# Actuadores.net
KiCad netlist of a schematic drawn in Altium Designer
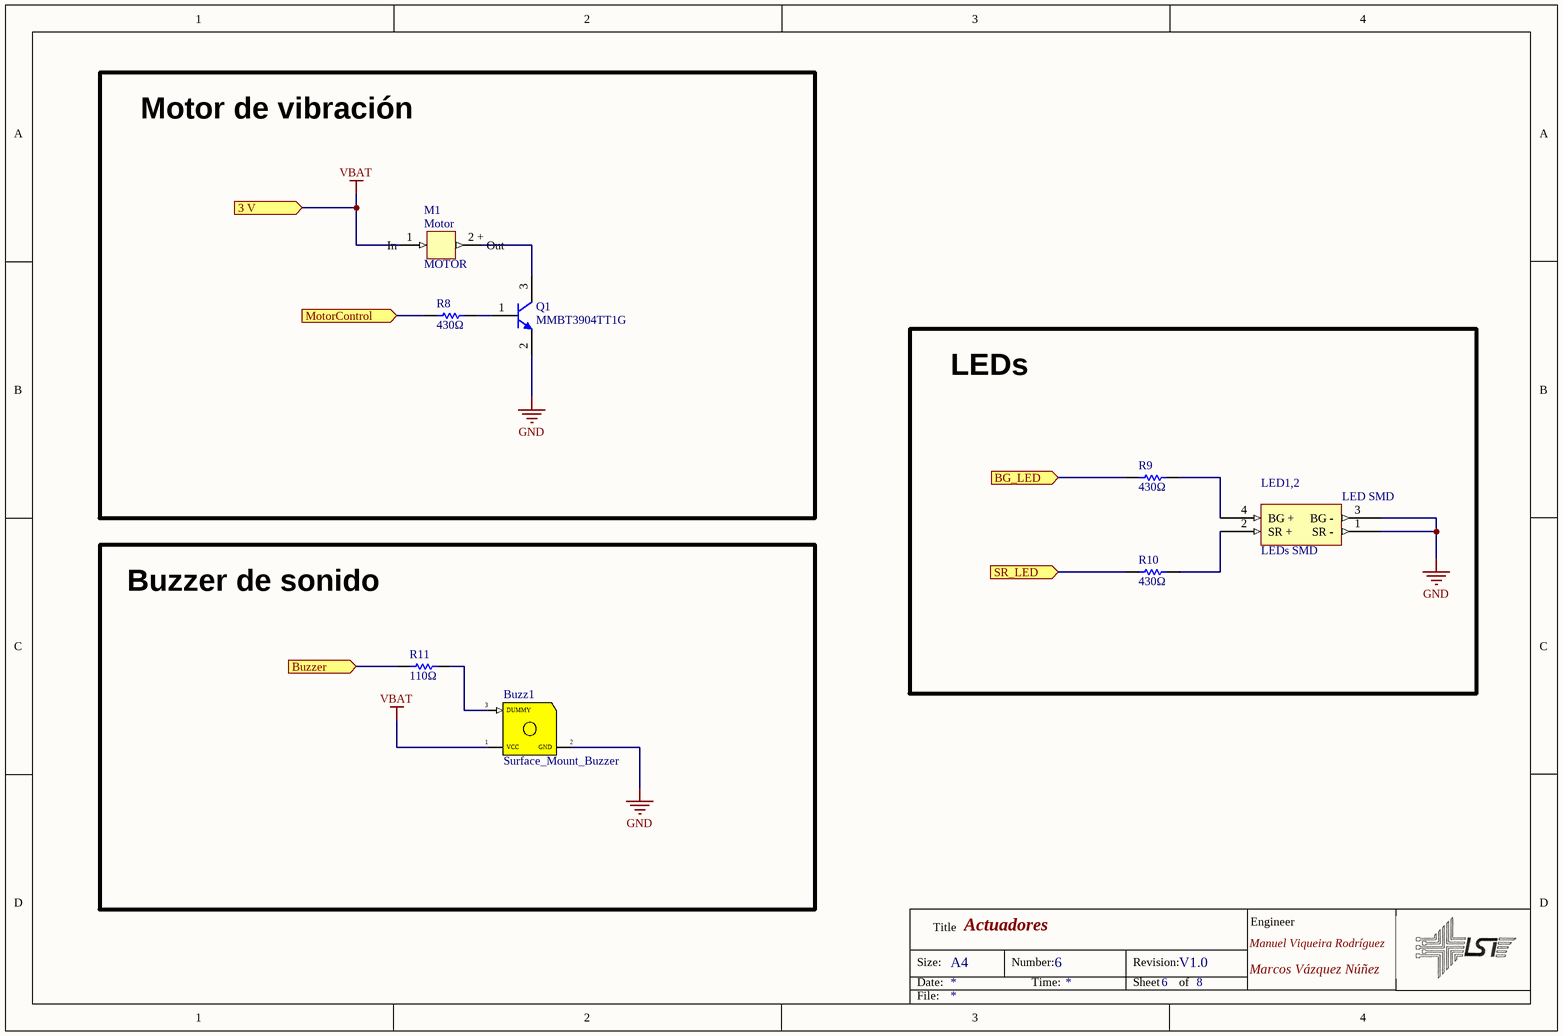
[diagram p0: Actuadores.SchDoc]

(export (version "E")
  (design (tool "Eeschema 10.0.6"))
  (components
    (comp (ref "Buzz1")
      (value "Surface_Mount_Buzzer")
      (footprint "buzzer")
      (libsource (lib "DEOP2021") (part "Surface_Mount_Buzzer"))
    )
    (comp (ref "LED1,2") (value "LEDs SMD") (footprint "LED_SMD") (libsource (lib "DEOP2021") (part "LED")))
    (comp (ref "M1") (value "MOTOR") (footprint "Motor") (libsource (lib "DEOP2021") (part "MOTOR")))
    (comp (ref "Q1")
      (value "MMBT3904TT1G")
      (footprint "ONSC-SC-75-3-463-01_V")
      (description "General Purpose Transistor, NPN Silicon, 3-Pin SC-75, Pb-Free, Tape and Reel")
      (fields (field (name "MANUFACTURER") "On Semiconductor"))
      (libsource (lib "Altium Content Vault") (part "ONSC-NPN-B1E2C3-3"))
    )
    (comp (ref "R8")
      (value "430Ω")
      (footprint "RESC0603X28X15ML05T05")
      (fields (field (name "MANUFACTURER") "Vishay Dale") (field (name "PART NUMBER") "CRCW020120K0JNED"))
      (libsource (lib "Altium Content Vault") (part "RES"))
    )
    (comp (ref "R9")
      (value "430Ω")
      (footprint "RESC0603X28X15ML05T05")
      (fields (field (name "MANUFACTURER") "Vishay Dale") (field (name "PART NUMBER") "CRCW020120K0JNED"))
      (libsource (lib "Altium Content Vault") (part "RES"))
    )
    (comp (ref "R10")
      (value "430Ω")
      (footprint "RESC0603X28X15ML05T05")
      (fields (field (name "MANUFACTURER") "Vishay Dale") (field (name "PART NUMBER") "CRCW020120K0JNED"))
      (libsource (lib "Altium Content Vault") (part "RES"))
    )
    (comp (ref "R11")
      (value "110Ω")
      (footprint "RESC0603X28X15ML05T05")
      (fields (field (name "MANUFACTURER") "Vishay Dale") (field (name "PART NUMBER") "CRCW020120K0JNED"))
      (libsource (lib "Altium Content Vault") (part "RES"))
    )
  )
  (nets
    (net (code "1") (name "/BG_LED") (class "Default")
      (node (ref "R9") (pin "1") (pinfunction "1_1") (pintype "passive"))
    )
    (net (code "2") (name "/Buzzer") (class "Default")
      (node (ref "R11") (pin "1") (pinfunction "1_1") (pintype "passive"))
    )
    (net (code "3") (name "/MotorControl") (class "Default")
      (node (ref "R8") (pin "1") (pinfunction "1_1") (pintype "passive"))
    )
    (net (code "4") (name "/SR_LED") (class "Default")
      (node (ref "R10") (pin "1") (pinfunction "1_1") (pintype "passive"))
    )
    (net (code "5") (name "GND") (class "Default")
      (node (ref "Buzz1") (pin "2") (pinfunction "GND_2") (pintype "power_in"))
      (node (ref "LED1,2") (pin "1") (pinfunction "SR_-_1") (pintype "output"))
      (node (ref "LED1,2") (pin "3") (pinfunction "BG_-_3") (pintype "output"))
      (node (ref "Q1") (pin "2") (pinfunction "E_2") (pintype "passive"))
    )
    (net (code "6") (name "Net-(Buzz1-DUMMY)") (class "Default")
      (node (ref "Buzz1") (pin "3") (pinfunction "DUMMY_3") (pintype "input"))
      (node (ref "R11") (pin "2") (pinfunction "2_2") (pintype "passive"))
    )
    (net (code "7") (name "Net-(LED1,2-BG_+)") (class "Default")
      (node (ref "LED1,2") (pin "4") (pinfunction "BG_+_4") (pintype "input"))
      (node (ref "R9") (pin "2") (pinfunction "2_2") (pintype "passive"))
    )
    (net (code "8") (name "Net-(LED1,2-SR_+)") (class "Default")
      (node (ref "LED1,2") (pin "2") (pinfunction "SR_+_2") (pintype "input"))
      (node (ref "R10") (pin "2") (pinfunction "2_2") (pintype "passive"))
    )
    (net (code "9") (name "Net-(M1-Out)") (class "Default")
      (node (ref "M1") (pin "2_+") (pinfunction "Out_2_+") (pintype "output"))
      (node (ref "Q1") (pin "3") (pinfunction "C_3") (pintype "passive"))
    )
    (net (code "10") (name "Net-(Q1-B)") (class "Default")
      (node (ref "Q1") (pin "1") (pinfunction "B_1") (pintype "passive"))
      (node (ref "R8") (pin "2") (pinfunction "2_2") (pintype "passive"))
    )
    (net (code "11") (name "VBAT") (class "Default")
      (node (ref "Buzz1") (pin "1") (pinfunction "VCC_1") (pintype "power_in"))
      (node (ref "M1") (pin "1") (pinfunction "In_1") (pintype "input"))
    )
  )
)
